# gwx-3p-control-oc.net
KiCad netlist of a schematic drawn in EAGLE
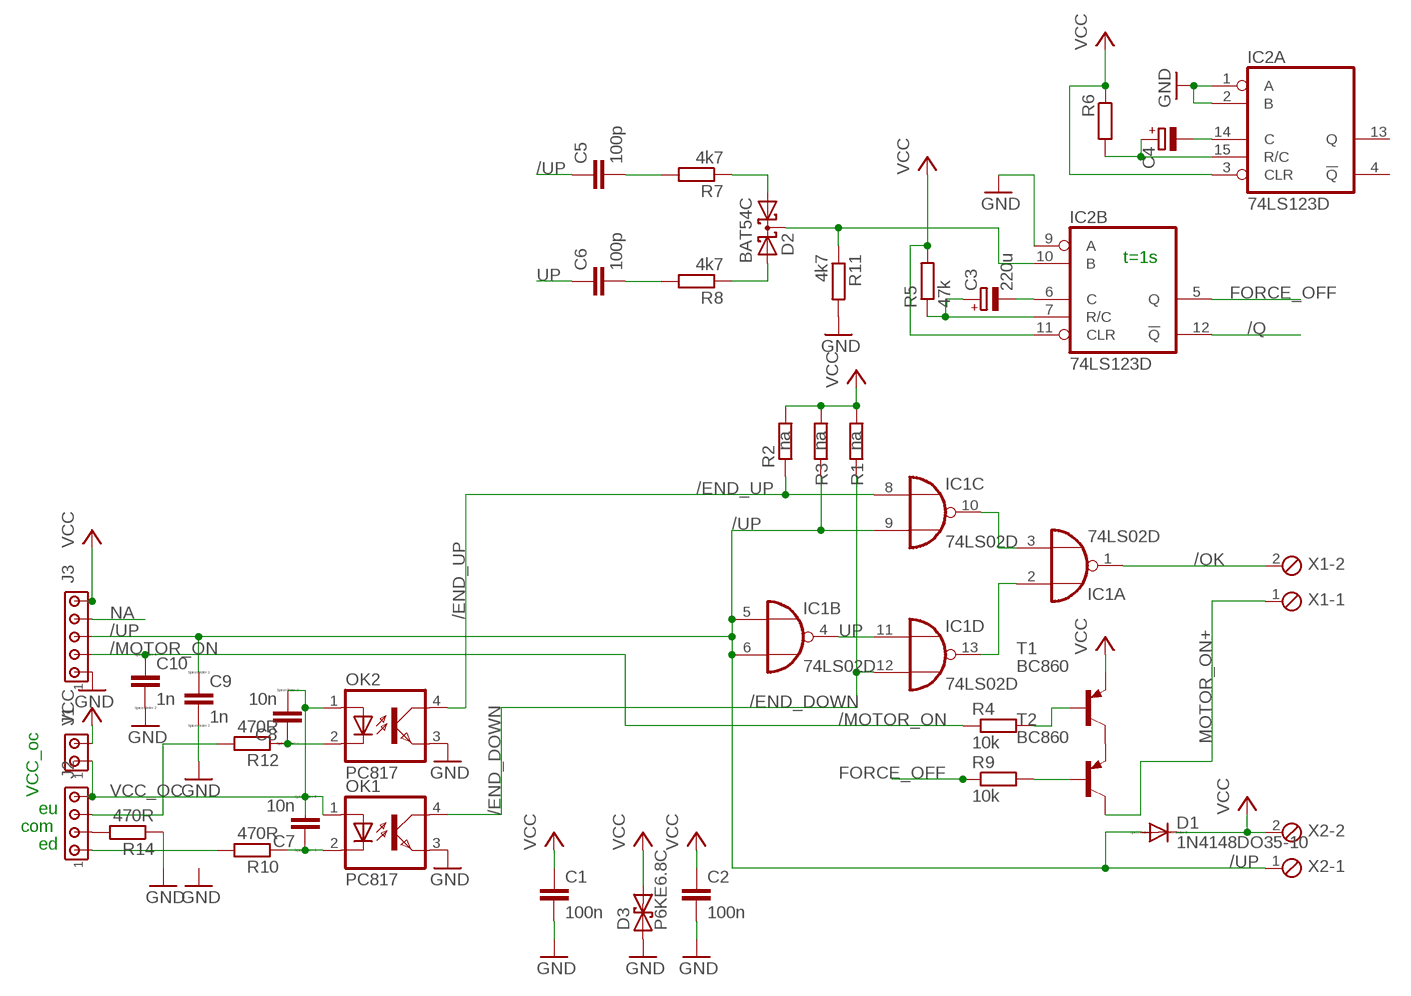
[diagram p0: schematic, sheet 1]

(export (version "E")
  (design (tool "Eeschema 10.0.6"))
  (components
    (comp (ref "C1")
      (value "100n")
      (footprint "eagle-import:C0603K")
      (libsource (lib "eagle-import") (part "C-EUC0603K"))
    )
    (comp (ref "C2")
      (value "100n")
      (footprint "eagle-import:C0603K")
      (libsource (lib "eagle-import") (part "C-EUC0603K"))
    )
    (comp (ref "C3")
      (value "220u")
      (footprint "eagle-import:E5-6")
      (libsource (lib "eagle-import") (part "CPOL-EUE5-6"))
    )
    (comp (ref "C4")
      (value "CPOL-EUE5-6")
      (footprint "eagle-import:E5-6")
      (libsource (lib "eagle-import") (part "CPOL-EUE5-6"))
    )
    (comp (ref "C5")
      (value "100p")
      (footprint "eagle-import:C0603K")
      (libsource (lib "eagle-import") (part "C-EUC0603K"))
    )
    (comp (ref "C6")
      (value "100p")
      (footprint "eagle-import:C0603K")
      (libsource (lib "eagle-import") (part "C-EUC0603K"))
    )
    (comp (ref "C7")
      (value "10n")
      (footprint "eagle-import:C0603")
      (libsource (lib "eagle-import") (part "CC0603"))
    )
    (comp (ref "C8")
      (value "10n")
      (footprint "eagle-import:C0603")
      (libsource (lib "eagle-import") (part "CC0603"))
    )
    (comp (ref "C9")
      (value "1n")
      (footprint "eagle-import:C0603")
      (libsource (lib "eagle-import") (part "CC0603"))
    )
    (comp (ref "C10")
      (value "1n")
      (footprint "eagle-import:C0603")
      (libsource (lib "eagle-import") (part "CC0603"))
    )
    (comp (ref "D1")
      (value "1N4148DO35-10")
      (footprint "eagle-import:DO35-10")
      (libsource (lib "eagle-import") (part "1N4148DO35-10"))
    )
    (comp (ref "D2")
      (value "BAT54C")
      (footprint "eagle-import:SOT23")
      (libsource (lib "eagle-import") (part "BAT54C"))
    )
    (comp (ref "D3")
      (value "P6KE6.8C")
      (footprint "eagle-import:CB417-15")
      (libsource (lib "eagle-import") (part "P6KEXXC"))
    )
    (comp (ref "IC1")
      (value "74LS02D")
      (footprint "eagle-import:SO14")
      (libsource (lib "eagle-import") (part "7402DLS"))
    )
    (comp (ref "IC2")
      (value "74LS123D")
      (footprint "eagle-import:SO16")
      (libsource (lib "eagle-import") (part "74123DLS"))
    )
    (comp (ref "J1")
      (value "MTA02-100")
      (footprint "eagle-import:10X02MTA")
      (libsource (lib "eagle-import") (part "MTA02-100"))
    )
    (comp (ref "J2")
      (value "MTA04-100")
      (footprint "eagle-import:10X04MTA")
      (libsource (lib "eagle-import") (part "MTA04-100"))
    )
    (comp (ref "J3")
      (value "MTA05-100")
      (footprint "eagle-import:10X05MTA")
      (libsource (lib "eagle-import") (part "MTA05-100"))
    )
    (comp (ref "OK1")
      (value "PC817")
      (footprint "eagle-import:DIL04")
      (fields (field (name "MPN") "PC817X4J000F"))
      (libsource (lib "eagle-import") (part "PC817"))
    )
    (comp (ref "OK2")
      (value "PC817")
      (footprint "eagle-import:DIL04")
      (fields (field (name "MPN") "PC817X4J000F"))
      (libsource (lib "eagle-import") (part "PC817"))
    )
    (comp (ref "R1")
      (value "na")
      (footprint "eagle-import:R0603")
      (libsource (lib "eagle-import") (part "resistor_R-EU_R0603"))
    )
    (comp (ref "R2")
      (value "na")
      (footprint "eagle-import:R0603")
      (libsource (lib "eagle-import") (part "resistor_R-EU_R0603"))
    )
    (comp (ref "R3")
      (value "na")
      (footprint "eagle-import:R0603")
      (libsource (lib "eagle-import") (part "resistor_R-EU_R0603"))
    )
    (comp (ref "R4")
      (value "10k")
      (footprint "eagle-import:R0603")
      (libsource (lib "eagle-import") (part "resistor_R-EU_R0603"))
    )
    (comp (ref "R5")
      (value "47k")
      (footprint "eagle-import:R0603")
      (libsource (lib "eagle-import") (part "R-EU_R0603"))
    )
    (comp (ref "R6")
      (value "R-EU_R0603")
      (footprint "eagle-import:R0603")
      (libsource (lib "eagle-import") (part "R-EU_R0603"))
    )
    (comp (ref "R7")
      (value "4k7")
      (footprint "eagle-import:R0603")
      (libsource (lib "eagle-import") (part "R-EU_R0603"))
    )
    (comp (ref "R8")
      (value "4k7")
      (footprint "eagle-import:R0603")
      (libsource (lib "eagle-import") (part "R-EU_R0603"))
    )
    (comp (ref "R9")
      (value "10k")
      (footprint "eagle-import:R0603")
      (libsource (lib "eagle-import") (part "resistor_R-EU_R0603"))
    )
    (comp (ref "R10")
      (value "470R")
      (footprint "eagle-import:R0603")
      (libsource (lib "eagle-import") (part "R-EU_R0603"))
    )
    (comp (ref "R11")
      (value "4k7")
      (footprint "eagle-import:R0603")
      (libsource (lib "eagle-import") (part "R-EU_R0603"))
    )
    (comp (ref "R12")
      (value "470R")
      (footprint "eagle-import:R0603")
      (libsource (lib "eagle-import") (part "R-EU_R0603"))
    )
    (comp (ref "R14")
      (value "470R")
      (footprint "eagle-import:R0603")
      (libsource (lib "eagle-import") (part "R-EU_R0603"))
    )
    (comp (ref "T1")
      (value "BC860")
      (footprint "eagle-import:SOT23-BEC")
      (libsource (lib "eagle-import") (part "-PNP-SOT23-BECBC856B"))
    )
    (comp (ref "T2")
      (value "BC860")
      (footprint "eagle-import:SOT23-BEC")
      (libsource (lib "eagle-import") (part "-PNP-SOT23-BECBC856B"))
    )
    (comp (ref "X1")
      (value "MPT2")
      (footprint "eagle-import:2POL254")
      (libsource (lib "eagle-import") (part "MPT2"))
    )
    (comp (ref "X2")
      (value "MPT2")
      (footprint "eagle-import:2POL254")
      (libsource (lib "eagle-import") (part "MPT2"))
    )
  )
  (nets
    (net (code "1") (name "/FORCE_OFF") (class "Default")
      (node (ref "IC2") (pin "5") (pinfunction "Q_5") (pintype "output"))
      (node (ref "R9") (pin "1") (pinfunction "1_1") (pintype "passive"))
    )
    (net (code "2") (name "/MOTOR_ON+") (class "Default")
      (node (ref "T2") (pin "C") (pinfunction "C_C") (pintype "passive"))
      (node (ref "X1") (pin "1") (pinfunction "1_1") (pintype "passive"))
    )
    (net (code "3") (name "/NA") (class "Default")
      (node (ref "J3") (pin "4") (pinfunction "4_4") (pintype "passive"))
    )
    (net (code "4") (name "/UP") (class "Default")
      (node (ref "C6") (pin "1") (pinfunction "1_1") (pintype "passive"))
      (node (ref "IC1") (pin "11") (pinfunction "I0_11") (pintype "input"))
      (node (ref "IC1") (pin "4") (pinfunction "O_4") (pintype "output"))
    )
    (net (code "5") (name "/VCC_OC") (class "Default")
      (node (ref "C7") (pin "2") (pinfunction "2_2") (pintype "passive"))
      (node (ref "C8") (pin "2") (pinfunction "2_2") (pintype "passive"))
      (node (ref "J1") (pin "1") (pinfunction "1_1") (pintype "passive"))
      (node (ref "J2") (pin "4") (pinfunction "4_4") (pintype "passive"))
      (node (ref "OK1") (pin "1") (pinfunction "A_1") (pintype "passive"))
      (node (ref "OK2") (pin "1") (pinfunction "A_1") (pintype "passive"))
    )
    (net (code "6") (name "/{slash}END_DOWN") (class "Default")
      (node (ref "IC1") (pin "12") (pinfunction "I1_12") (pintype "input"))
      (node (ref "OK1") (pin "4") (pinfunction "COL_4") (pintype "passive"))
      (node (ref "R1") (pin "1") (pinfunction "1_1") (pintype "passive"))
    )
    (net (code "7") (name "/{slash}END_UP") (class "Default")
      (node (ref "IC1") (pin "8") (pinfunction "I0_8") (pintype "input"))
      (node (ref "OK2") (pin "4") (pinfunction "COL_4") (pintype "passive"))
      (node (ref "R2") (pin "1") (pinfunction "1_1") (pintype "passive"))
    )
    (net (code "8") (name "/{slash}MOTOR_ON") (class "Default")
      (node (ref "C10") (pin "1") (pinfunction "1_1") (pintype "passive"))
      (node (ref "J3") (pin "2") (pinfunction "2_2") (pintype "passive"))
      (node (ref "R4") (pin "1") (pinfunction "1_1") (pintype "passive"))
    )
    (net (code "9") (name "/{slash}OK") (class "Default")
      (node (ref "IC1") (pin "1") (pinfunction "O_1") (pintype "output"))
      (node (ref "X1") (pin "2") (pinfunction "1_2") (pintype "passive"))
    )
    (net (code "10") (name "/{slash}Q") (class "Default")
      (node (ref "IC2") (pin "12") (pinfunction "~{Q}_12") (pintype "output"))
    )
    (net (code "11") (name "/{slash}UP") (class "Default")
      (node (ref "C5") (pin "1") (pinfunction "1_1") (pintype "passive"))
      (node (ref "C9") (pin "1") (pinfunction "1_1") (pintype "passive"))
      (node (ref "D1") (pin "A") (pinfunction "A_A") (pintype "passive"))
      (node (ref "IC1") (pin "5") (pinfunction "I0_5") (pintype "input"))
      (node (ref "IC1") (pin "6") (pinfunction "I1_6") (pintype "input"))
      (node (ref "IC1") (pin "9") (pinfunction "I1_9") (pintype "input"))
      (node (ref "J3") (pin "3") (pinfunction "3_3") (pintype "passive"))
      (node (ref "R3") (pin "1") (pinfunction "1_1") (pintype "passive"))
      (node (ref "X2") (pin "1") (pinfunction "1_1") (pintype "passive"))
    )
    (net (code "12") (name "GND") (class "Default")
      (node (ref "C1") (pin "2") (pinfunction "2_2") (pintype "passive"))
      (node (ref "C10") (pin "2") (pinfunction "2_2") (pintype "passive"))
      (node (ref "C2") (pin "2") (pinfunction "2_2") (pintype "passive"))
      (node (ref "C9") (pin "2") (pinfunction "2_2") (pintype "passive"))
      (node (ref "D3") (pin "A") (pinfunction "1_A") (pintype "passive"))
      (node (ref "IC2") (pin "1") (pinfunction "A_1") (pintype "input"))
      (node (ref "IC2") (pin "2") (pinfunction "B_2") (pintype "input"))
      (node (ref "IC2") (pin "9") (pinfunction "A_9") (pintype "input"))
      (node (ref "J3") (pin "1") (pinfunction "1_1") (pintype "passive"))
      (node (ref "OK1") (pin "3") (pinfunction "EMIT_3") (pintype "passive"))
      (node (ref "OK2") (pin "3") (pinfunction "EMIT_3") (pintype "passive"))
      (node (ref "R11") (pin "2") (pinfunction "2_2") (pintype "passive"))
      (node (ref "R14") (pin "1") (pinfunction "1_1") (pintype "passive"))
    )
    (net (code "13") (name "Net-(C5-Pad2)") (class "Default")
      (node (ref "C5") (pin "2") (pinfunction "2_2") (pintype "passive"))
      (node (ref "R7") (pin "2") (pinfunction "2_2") (pintype "passive"))
    )
    (net (code "14") (name "Net-(C6-Pad2)") (class "Default")
      (node (ref "C6") (pin "2") (pinfunction "2_2") (pintype "passive"))
      (node (ref "R8") (pin "2") (pinfunction "2_2") (pintype "passive"))
    )
    (net (code "15") (name "Net-(D2-A1)") (class "Default")
      (node (ref "D2") (pin "1") (pinfunction "A1_1") (pintype "passive"))
      (node (ref "R7") (pin "1") (pinfunction "1_1") (pintype "passive"))
    )
    (net (code "16") (name "Net-(D2-A2)") (class "Default")
      (node (ref "D2") (pin "2") (pinfunction "A2_2") (pintype "passive"))
      (node (ref "R8") (pin "1") (pinfunction "1_1") (pintype "passive"))
    )
    (net (code "17") (name "Net-(D2-CC)") (class "Default")
      (node (ref "D2") (pin "3") (pinfunction "CC_3") (pintype "passive"))
      (node (ref "IC2") (pin "10") (pinfunction "B_10") (pintype "input"))
      (node (ref "R11") (pin "1") (pinfunction "1_1") (pintype "passive"))
    )
    (net (code "18") (name "Net-(IC1A-I0)") (class "Default")
      (node (ref "IC1") (pin "13") (pinfunction "O_13") (pintype "output"))
      (node (ref "IC1") (pin "2") (pinfunction "I0_2") (pintype "input"))
    )
    (net (code "19") (name "Net-(IC1A-I1)") (class "Default")
      (node (ref "IC1") (pin "10") (pinfunction "O_10") (pintype "output"))
      (node (ref "IC1") (pin "3") (pinfunction "I1_3") (pintype "input"))
    )
    (net (code "20") (name "Net-(IC2A-C)") (class "Default")
      (node (ref "C4") (pin "-") (pinfunction "-_-") (pintype "passive"))
      (node (ref "IC2") (pin "14") (pinfunction "C_14") (pintype "input"))
    )
    (net (code "21") (name "Net-(IC2A-R{slash}C)") (class "Default")
      (node (ref "C4") (pin "+") (pinfunction "+_+") (pintype "passive"))
      (node (ref "IC2") (pin "15") (pinfunction "R/C_15") (pintype "input"))
      (node (ref "R6") (pin "2") (pinfunction "2_2") (pintype "passive"))
    )
    (net (code "22") (name "Net-(IC2B-C)") (class "Default")
      (node (ref "C3") (pin "-") (pinfunction "-_-") (pintype "passive"))
      (node (ref "IC2") (pin "6") (pinfunction "C_6") (pintype "input"))
    )
    (net (code "23") (name "Net-(IC2B-R{slash}C)") (class "Default")
      (node (ref "C3") (pin "+") (pinfunction "+_+") (pintype "passive"))
      (node (ref "IC2") (pin "7") (pinfunction "R/C_7") (pintype "input"))
      (node (ref "R5") (pin "1") (pinfunction "1_1") (pintype "passive"))
    )
    (net (code "24") (name "Net-(J2-Pad1)") (class "Default")
      (node (ref "J2") (pin "1") (pinfunction "1_1") (pintype "passive"))
      (node (ref "R10") (pin "2") (pinfunction "2_2") (pintype "passive"))
    )
    (net (code "25") (name "Net-(J2-Pad2)") (class "Default")
      (node (ref "J2") (pin "2") (pinfunction "2_2") (pintype "passive"))
      (node (ref "R14") (pin "2") (pinfunction "2_2") (pintype "passive"))
    )
    (net (code "26") (name "Net-(J2-Pad3)") (class "Default")
      (node (ref "J2") (pin "3") (pinfunction "3_3") (pintype "passive"))
      (node (ref "R12") (pin "2") (pinfunction "2_2") (pintype "passive"))
    )
    (net (code "27") (name "Net-(OK1-C)") (class "Default")
      (node (ref "C7") (pin "1") (pinfunction "1_1") (pintype "passive"))
      (node (ref "OK1") (pin "2") (pinfunction "C_2") (pintype "passive"))
      (node (ref "R10") (pin "1") (pinfunction "1_1") (pintype "passive"))
    )
    (net (code "28") (name "Net-(OK2-C)") (class "Default")
      (node (ref "C8") (pin "1") (pinfunction "1_1") (pintype "passive"))
      (node (ref "OK2") (pin "2") (pinfunction "C_2") (pintype "passive"))
      (node (ref "R12") (pin "1") (pinfunction "1_1") (pintype "passive"))
    )
    (net (code "29") (name "Net-(R4-Pad2)") (class "Default")
      (node (ref "R4") (pin "2") (pinfunction "2_2") (pintype "passive"))
      (node (ref "T1") (pin "B") (pinfunction "B_B") (pintype "passive"))
    )
    (net (code "30") (name "Net-(R9-Pad2)") (class "Default")
      (node (ref "R9") (pin "2") (pinfunction "2_2") (pintype "passive"))
      (node (ref "T2") (pin "B") (pinfunction "B_B") (pintype "passive"))
    )
    (net (code "31") (name "Net-(T1-PadC)") (class "Default")
      (node (ref "T1") (pin "C") (pinfunction "C_C") (pintype "passive"))
      (node (ref "T2") (pin "E") (pinfunction "E_E") (pintype "passive"))
    )
    (net (code "32") (name "VCC") (class "Default")
      (node (ref "C1") (pin "1") (pinfunction "1_1") (pintype "passive"))
      (node (ref "C2") (pin "1") (pinfunction "1_1") (pintype "passive"))
      (node (ref "D1") (pin "C") (pinfunction "C_C") (pintype "passive"))
      (node (ref "D3") (pin "C") (pinfunction "2_C") (pintype "passive"))
      (node (ref "IC2") (pin "11") (pinfunction "CLR_11") (pintype "input"))
      (node (ref "IC2") (pin "3") (pinfunction "CLR_3") (pintype "input"))
      (node (ref "J1") (pin "2") (pinfunction "2_2") (pintype "passive"))
      (node (ref "J3") (pin "5") (pinfunction "5_5") (pintype "passive"))
      (node (ref "R1") (pin "2") (pinfunction "2_2") (pintype "passive"))
      (node (ref "R2") (pin "2") (pinfunction "2_2") (pintype "passive"))
      (node (ref "R3") (pin "2") (pinfunction "2_2") (pintype "passive"))
      (node (ref "R5") (pin "2") (pinfunction "2_2") (pintype "passive"))
      (node (ref "R6") (pin "1") (pinfunction "1_1") (pintype "passive"))
      (node (ref "T1") (pin "E") (pinfunction "E_E") (pintype "passive"))
      (node (ref "X2") (pin "2") (pinfunction "1_2") (pintype "passive"))
    )
    (net (code "33") (name "unconnected-(IC2A-Q-Pad13)") (class "Default")
      (node (ref "IC2") (pin "13") (pinfunction "Q_13") (pintype "output"))
    )
    (net (code "34") (name "unconnected-(IC2A-~{Q}-Pad4)") (class "Default")
      (node (ref "IC2") (pin "4") (pinfunction "~{Q}_4") (pintype "output"))
    )
  )
)
